# k210-board.net
KiCad netlist of a schematic drawn in Altium Designer
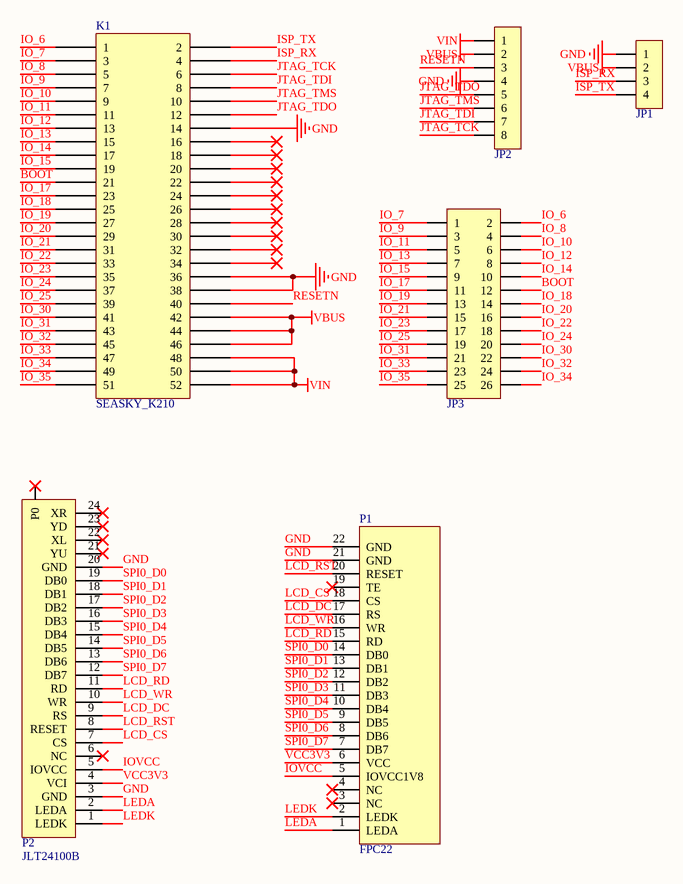
[diagram p0: k210-board.SchDoc]

(export (version "E")
  (design (tool "Eeschema 10.0.6"))
  (components
    (comp (ref "JP1")
      (value "HDR-1X4")
      (footprint "MX 1.25-WS-4P")
      (description "4P接插件")
      (libsource (lib "5.0 - 接插件-脚距1.25") (part "Header 4"))
    )
    (comp (ref "JP2")
      (value "HDR-1X8")
      (footprint "MX 1.25-WS-8P")
      (description "8P接插件")
      (libsource (lib "5.0 - 接插件-脚距1.25") (part "Header 8"))
    )
    (comp (ref "JP3")
      (value "Header 2X11")
      (footprint "HDR2.54-LI-2x13P")
      (description "13*2P接插件")
      (libsource (lib "5.3 - 接插件-脚距2.54 (100mil) ") (part "Header 13X2"))
    )
    (comp (ref "K1")
      (value "SEASKY_K210")
      (footprint "SEASKY_K210")
      (description "mini-PCI-E")
      (libsource (lib "Schlib1") (part "SEASKY_K210"))
    )
    (comp (ref "P1")
      (value "FPC22")
      (footprint "FPC0.5 2H-WS-22P")
      (libsource (lib "Schlib1") (part "FPC22"))
    )
    (comp (ref "P2")
      (value "JLT24100B")
      (footprint "FFC/SM0.5-2H24-LCD")
      (fields (field (name "PUBLISHER") "Altium Limited"))
      (libsource (lib "Schlib1") (part "JLT24100B"))
    )
  )
  (nets
    (net (code "1") (name "/BOOT") (class "Default")
      (node (ref "JP3") (pin "12") (pinfunction "12_12") (pintype "passive"))
      (node (ref "K1") (pin "21") (pinfunction "21_21") (pintype "passive"))
    )
    (net (code "2") (name "/IOVCC") (class "Default")
      (node (ref "P1") (pin "5") (pinfunction "IOVCC1V8_5") (pintype "passive"))
      (node (ref "P2") (pin "5") (pinfunction "IOVCC_5") (pintype "passive"))
    )
    (net (code "3") (name "/IO_6") (class "Default")
      (node (ref "JP3") (pin "2") (pinfunction "2_2") (pintype "passive"))
      (node (ref "K1") (pin "1") (pinfunction "1_1") (pintype "passive"))
    )
    (net (code "4") (name "/IO_7") (class "Default")
      (node (ref "JP3") (pin "1") (pinfunction "1_1") (pintype "passive"))
      (node (ref "K1") (pin "3") (pinfunction "3_3") (pintype "passive"))
    )
    (net (code "5") (name "/IO_8") (class "Default")
      (node (ref "JP3") (pin "4") (pinfunction "4_4") (pintype "passive"))
      (node (ref "K1") (pin "5") (pinfunction "5_5") (pintype "passive"))
    )
    (net (code "6") (name "/IO_9") (class "Default")
      (node (ref "JP3") (pin "3") (pinfunction "3_3") (pintype "passive"))
      (node (ref "K1") (pin "7") (pinfunction "7_7") (pintype "passive"))
    )
    (net (code "7") (name "/IO_10") (class "Default")
      (node (ref "JP3") (pin "6") (pinfunction "6_6") (pintype "passive"))
      (node (ref "K1") (pin "9") (pinfunction "9_9") (pintype "passive"))
    )
    (net (code "8") (name "/IO_11") (class "Default")
      (node (ref "JP3") (pin "5") (pinfunction "5_5") (pintype "passive"))
      (node (ref "K1") (pin "11") (pinfunction "11_11") (pintype "passive"))
    )
    (net (code "9") (name "/IO_12") (class "Default")
      (node (ref "JP3") (pin "8") (pinfunction "8_8") (pintype "passive"))
      (node (ref "K1") (pin "13") (pinfunction "13_13") (pintype "passive"))
    )
    (net (code "10") (name "/IO_13") (class "Default")
      (node (ref "JP3") (pin "7") (pinfunction "7_7") (pintype "passive"))
      (node (ref "K1") (pin "15") (pinfunction "15_15") (pintype "passive"))
    )
    (net (code "11") (name "/IO_14") (class "Default")
      (node (ref "JP3") (pin "10") (pinfunction "10_10") (pintype "passive"))
      (node (ref "K1") (pin "17") (pinfunction "17_17") (pintype "passive"))
    )
    (net (code "12") (name "/IO_15") (class "Default")
      (node (ref "JP3") (pin "9") (pinfunction "9_9") (pintype "passive"))
      (node (ref "K1") (pin "19") (pinfunction "19_19") (pintype "passive"))
    )
    (net (code "13") (name "/IO_17") (class "Default")
      (node (ref "JP3") (pin "11") (pinfunction "11_11") (pintype "passive"))
      (node (ref "K1") (pin "23") (pinfunction "23_23") (pintype "passive"))
    )
    (net (code "14") (name "/IO_18") (class "Default")
      (node (ref "JP3") (pin "14") (pinfunction "14_14") (pintype "passive"))
      (node (ref "K1") (pin "25") (pinfunction "25_25") (pintype "passive"))
    )
    (net (code "15") (name "/IO_19") (class "Default")
      (node (ref "JP3") (pin "13") (pinfunction "13_13") (pintype "passive"))
      (node (ref "K1") (pin "27") (pinfunction "27_27") (pintype "passive"))
    )
    (net (code "16") (name "/IO_20") (class "Default")
      (node (ref "JP3") (pin "16") (pinfunction "16_16") (pintype "passive"))
      (node (ref "K1") (pin "29") (pinfunction "29_29") (pintype "passive"))
    )
    (net (code "17") (name "/IO_21") (class "Default")
      (node (ref "JP3") (pin "15") (pinfunction "15_15") (pintype "passive"))
      (node (ref "K1") (pin "31") (pinfunction "31_31") (pintype "passive"))
    )
    (net (code "18") (name "/IO_22") (class "Default")
      (node (ref "JP3") (pin "18") (pinfunction "18_18") (pintype "passive"))
      (node (ref "K1") (pin "33") (pinfunction "33_33") (pintype "passive"))
    )
    (net (code "19") (name "/IO_23") (class "Default")
      (node (ref "JP3") (pin "17") (pinfunction "17_17") (pintype "passive"))
      (node (ref "K1") (pin "35") (pinfunction "35_35") (pintype "passive"))
    )
    (net (code "20") (name "/IO_24") (class "Default")
      (node (ref "JP3") (pin "20") (pinfunction "20_20") (pintype "passive"))
      (node (ref "K1") (pin "37") (pinfunction "37_37") (pintype "passive"))
    )
    (net (code "21") (name "/IO_25") (class "Default")
      (node (ref "JP3") (pin "19") (pinfunction "19_19") (pintype "passive"))
      (node (ref "K1") (pin "39") (pinfunction "39_39") (pintype "passive"))
    )
    (net (code "22") (name "/IO_30") (class "Default")
      (node (ref "JP3") (pin "22") (pinfunction "22_22") (pintype "passive"))
      (node (ref "K1") (pin "41") (pinfunction "41_41") (pintype "passive"))
    )
    (net (code "23") (name "/IO_31") (class "Default")
      (node (ref "JP3") (pin "21") (pinfunction "21_21") (pintype "passive"))
      (node (ref "K1") (pin "43") (pinfunction "43_43") (pintype "passive"))
    )
    (net (code "24") (name "/IO_32") (class "Default")
      (node (ref "JP3") (pin "24") (pinfunction "24_24") (pintype "passive"))
      (node (ref "K1") (pin "45") (pinfunction "45_45") (pintype "passive"))
    )
    (net (code "25") (name "/IO_33") (class "Default")
      (node (ref "JP3") (pin "23") (pinfunction "23_23") (pintype "passive"))
      (node (ref "K1") (pin "47") (pinfunction "47_47") (pintype "passive"))
    )
    (net (code "26") (name "/IO_34") (class "Default")
      (node (ref "JP3") (pin "26") (pinfunction "26_26") (pintype "passive"))
      (node (ref "K1") (pin "49") (pinfunction "49_49") (pintype "passive"))
    )
    (net (code "27") (name "/IO_35") (class "Default")
      (node (ref "JP3") (pin "25") (pinfunction "25_25") (pintype "passive"))
      (node (ref "K1") (pin "51") (pinfunction "51_51") (pintype "passive"))
    )
    (net (code "28") (name "/ISP_RX") (class "Default")
      (node (ref "JP1") (pin "3") (pinfunction "3_3") (pintype "passive"))
      (node (ref "K1") (pin "4") (pinfunction "4_4") (pintype "passive"))
    )
    (net (code "29") (name "/ISP_TX") (class "Default")
      (node (ref "JP1") (pin "4") (pinfunction "4_4") (pintype "passive"))
      (node (ref "K1") (pin "2") (pinfunction "2_2") (pintype "passive"))
    )
    (net (code "30") (name "/JTAG_TCK") (class "Default")
      (node (ref "JP2") (pin "8") (pinfunction "8_8") (pintype "passive"))
      (node (ref "K1") (pin "6") (pinfunction "6_6") (pintype "passive"))
    )
    (net (code "31") (name "/JTAG_TDI") (class "Default")
      (node (ref "JP2") (pin "7") (pinfunction "7_7") (pintype "passive"))
      (node (ref "K1") (pin "8") (pinfunction "8_8") (pintype "passive"))
    )
    (net (code "32") (name "/JTAG_TDO") (class "Default")
      (node (ref "JP2") (pin "5") (pinfunction "5_5") (pintype "passive"))
      (node (ref "K1") (pin "12") (pinfunction "12_12") (pintype "passive"))
    )
    (net (code "33") (name "/JTAG_TMS") (class "Default")
      (node (ref "JP2") (pin "6") (pinfunction "6_6") (pintype "passive"))
      (node (ref "K1") (pin "10") (pinfunction "10_10") (pintype "passive"))
    )
    (net (code "34") (name "/LCD_CS") (class "Default")
      (node (ref "P1") (pin "18") (pinfunction "CS_18") (pintype "passive"))
      (node (ref "P2") (pin "7") (pinfunction "CS_7") (pintype "passive"))
    )
    (net (code "35") (name "/LCD_DC") (class "Default")
      (node (ref "P1") (pin "17") (pinfunction "RS_17") (pintype "passive"))
      (node (ref "P2") (pin "9") (pinfunction "RS_9") (pintype "passive"))
    )
    (net (code "36") (name "/LCD_RD") (class "Default")
      (node (ref "P1") (pin "15") (pinfunction "RD_15") (pintype "passive"))
      (node (ref "P2") (pin "11") (pinfunction "RD_11") (pintype "passive"))
    )
    (net (code "37") (name "/LCD_RST") (class "Default")
      (node (ref "P1") (pin "20") (pinfunction "RESET_20") (pintype "passive"))
      (node (ref "P2") (pin "8") (pinfunction "RESET_8") (pintype "passive"))
    )
    (net (code "38") (name "/LCD_WR") (class "Default")
      (node (ref "P1") (pin "16") (pinfunction "WR_16") (pintype "passive"))
      (node (ref "P2") (pin "10") (pinfunction "WR_10") (pintype "passive"))
    )
    (net (code "39") (name "/LEDA") (class "Default")
      (node (ref "P1") (pin "1") (pinfunction "LEDA_1") (pintype "passive"))
      (node (ref "P2") (pin "2") (pinfunction "LEDA_2") (pintype "passive"))
    )
    (net (code "40") (name "/LEDK") (class "Default")
      (node (ref "P1") (pin "2") (pinfunction "LEDK_2") (pintype "passive"))
      (node (ref "P2") (pin "1") (pinfunction "LEDK_1") (pintype "passive"))
    )
    (net (code "41") (name "/RESETN") (class "Default")
      (node (ref "JP2") (pin "3") (pinfunction "3_3") (pintype "passive"))
      (node (ref "K1") (pin "40") (pinfunction "40_40") (pintype "passive"))
    )
    (net (code "42") (name "/SPI0_D0") (class "Default")
      (node (ref "P1") (pin "14") (pinfunction "DB0_14") (pintype "passive"))
      (node (ref "P2") (pin "19") (pinfunction "DB0_19") (pintype "passive"))
    )
    (net (code "43") (name "/SPI0_D1") (class "Default")
      (node (ref "P1") (pin "13") (pinfunction "DB1_13") (pintype "passive"))
      (node (ref "P2") (pin "18") (pinfunction "DB1_18") (pintype "passive"))
    )
    (net (code "44") (name "/SPI0_D2") (class "Default")
      (node (ref "P1") (pin "12") (pinfunction "DB2_12") (pintype "passive"))
      (node (ref "P2") (pin "17") (pinfunction "DB2_17") (pintype "passive"))
    )
    (net (code "45") (name "/SPI0_D3") (class "Default")
      (node (ref "P1") (pin "11") (pinfunction "DB3_11") (pintype "passive"))
      (node (ref "P2") (pin "16") (pinfunction "DB3_16") (pintype "passive"))
    )
    (net (code "46") (name "/SPI0_D4") (class "Default")
      (node (ref "P1") (pin "10") (pinfunction "DB4_10") (pintype "passive"))
      (node (ref "P2") (pin "15") (pinfunction "DB4_15") (pintype "passive"))
    )
    (net (code "47") (name "/SPI0_D5") (class "Default")
      (node (ref "P1") (pin "9") (pinfunction "DB5_9") (pintype "passive"))
      (node (ref "P2") (pin "14") (pinfunction "DB5_14") (pintype "passive"))
    )
    (net (code "48") (name "/SPI0_D6") (class "Default")
      (node (ref "P1") (pin "8") (pinfunction "DB6_8") (pintype "passive"))
      (node (ref "P2") (pin "13") (pinfunction "DB6_13") (pintype "passive"))
    )
    (net (code "49") (name "/SPI0_D7") (class "Default")
      (node (ref "P1") (pin "7") (pinfunction "DB7_7") (pintype "passive"))
      (node (ref "P2") (pin "12") (pinfunction "DB7_12") (pintype "passive"))
    )
    (net (code "50") (name "/VCC3V3") (class "Default")
      (node (ref "P1") (pin "6") (pinfunction "VCC_6") (pintype "passive"))
      (node (ref "P2") (pin "4") (pinfunction "VCI_4") (pintype "passive"))
    )
    (net (code "51") (name "GND") (class "Default")
      (node (ref "JP1") (pin "1") (pinfunction "1_1") (pintype "passive"))
      (node (ref "JP2") (pin "4") (pinfunction "4_4") (pintype "passive"))
      (node (ref "K1") (pin "14") (pinfunction "14_14") (pintype "passive"))
      (node (ref "K1") (pin "36") (pinfunction "36_36") (pintype "passive"))
      (node (ref "K1") (pin "38") (pinfunction "38_38") (pintype "passive"))
      (node (ref "P1") (pin "21") (pinfunction "GND_21") (pintype "passive"))
      (node (ref "P1") (pin "22") (pinfunction "GND_22") (pintype "passive"))
      (node (ref "P2") (pin "20") (pinfunction "GND_20") (pintype "passive"))
      (node (ref "P2") (pin "3") (pinfunction "GND_3") (pintype "passive"))
    )
    (net (code "52") (name "VBUS") (class "Default")
      (node (ref "JP1") (pin "2") (pinfunction "2_2") (pintype "passive"))
      (node (ref "JP2") (pin "2") (pinfunction "2_2") (pintype "passive"))
      (node (ref "K1") (pin "42") (pinfunction "42_42") (pintype "passive"))
      (node (ref "K1") (pin "44") (pinfunction "44_44") (pintype "passive"))
      (node (ref "K1") (pin "46") (pinfunction "46_46") (pintype "passive"))
    )
    (net (code "53") (name "VIN") (class "Default")
      (node (ref "JP2") (pin "1") (pinfunction "1_1") (pintype "passive"))
      (node (ref "K1") (pin "48") (pinfunction "48_48") (pintype "passive"))
      (node (ref "K1") (pin "50") (pinfunction "50_50") (pintype "passive"))
      (node (ref "K1") (pin "52") (pinfunction "52_52") (pintype "passive"))
    )
    (net (code "54") (name "unconnected-(K1-Pad16)") (class "Default")
      (node (ref "K1") (pin "16") (pinfunction "16_16") (pintype "passive+no_connect"))
    )
    (net (code "55") (name "unconnected-(K1-Pad18)") (class "Default")
      (node (ref "K1") (pin "18") (pinfunction "18_18") (pintype "passive+no_connect"))
    )
    (net (code "56") (name "unconnected-(K1-Pad20)") (class "Default")
      (node (ref "K1") (pin "20") (pinfunction "20_20") (pintype "passive+no_connect"))
    )
    (net (code "57") (name "unconnected-(K1-Pad22)") (class "Default")
      (node (ref "K1") (pin "22") (pinfunction "22_22") (pintype "passive+no_connect"))
    )
    (net (code "58") (name "unconnected-(K1-Pad24)") (class "Default")
      (node (ref "K1") (pin "24") (pinfunction "24_24") (pintype "passive+no_connect"))
    )
    (net (code "59") (name "unconnected-(K1-Pad26)") (class "Default")
      (node (ref "K1") (pin "26") (pinfunction "26_26") (pintype "passive+no_connect"))
    )
    (net (code "60") (name "unconnected-(K1-Pad28)") (class "Default")
      (node (ref "K1") (pin "28") (pinfunction "28_28") (pintype "passive+no_connect"))
    )
    (net (code "61") (name "unconnected-(K1-Pad30)") (class "Default")
      (node (ref "K1") (pin "30") (pinfunction "30_30") (pintype "passive+no_connect"))
    )
    (net (code "62") (name "unconnected-(K1-Pad32)") (class "Default")
      (node (ref "K1") (pin "32") (pinfunction "32_32") (pintype "passive+no_connect"))
    )
    (net (code "63") (name "unconnected-(K1-Pad34)") (class "Default")
      (node (ref "K1") (pin "34") (pinfunction "34_34") (pintype "passive+no_connect"))
    )
    (net (code "64") (name "unconnected-(P1-NC-Pad3)") (class "Default")
      (node (ref "P1") (pin "3") (pinfunction "NC_3") (pintype "passive+no_connect"))
    )
    (net (code "65") (name "unconnected-(P1-NC-Pad4)") (class "Default")
      (node (ref "P1") (pin "4") (pinfunction "NC_4") (pintype "passive+no_connect"))
    )
    (net (code "66") (name "unconnected-(P1-TE-Pad19)") (class "Default")
      (node (ref "P1") (pin "19") (pinfunction "TE_19") (pintype "passive+no_connect"))
    )
    (net (code "67") (name "unconnected-(P2-NC-Pad6)") (class "Default")
      (node (ref "P2") (pin "6") (pinfunction "NC_6") (pintype "passive+no_connect"))
    )
    (net (code "68") (name "unconnected-(P2-PadP0)") (class "Default")
      (node (ref "P2") (pin "P0") (pinfunction "P0_P0") (pintype "passive+no_connect"))
    )
    (net (code "69") (name "unconnected-(P2-XL-Pad22)") (class "Default")
      (node (ref "P2") (pin "22") (pinfunction "XL_22") (pintype "passive+no_connect"))
    )
    (net (code "70") (name "unconnected-(P2-XR-Pad24)") (class "Default")
      (node (ref "P2") (pin "24") (pinfunction "XR_24") (pintype "passive+no_connect"))
    )
    (net (code "71") (name "unconnected-(P2-YD-Pad23)") (class "Default")
      (node (ref "P2") (pin "23") (pinfunction "YD_23") (pintype "passive+no_connect"))
    )
    (net (code "72") (name "unconnected-(P2-YU-Pad21)") (class "Default")
      (node (ref "P2") (pin "21") (pinfunction "YU_21") (pintype "passive+no_connect"))
    )
  )
)
